# SERIALIO.net
KiCad netlist of a schematic drawn in Altium Designer
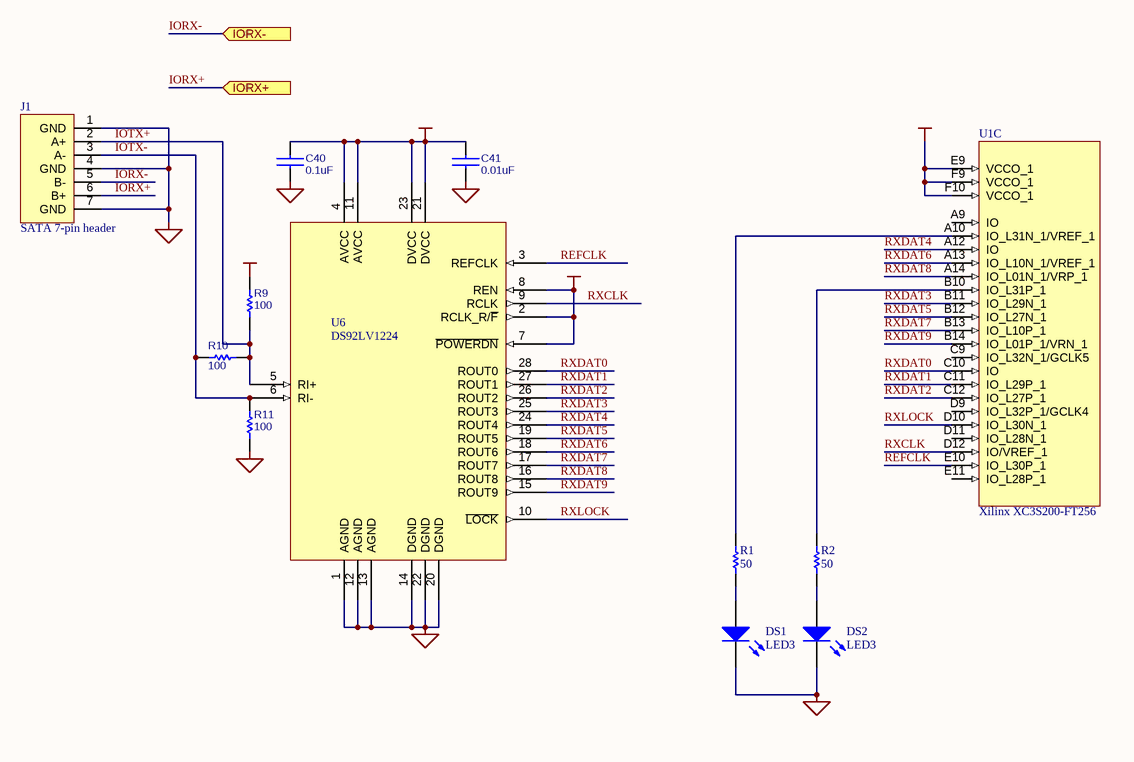
[diagram p0: SERIALIO.SCHDOC]

(export (version "E")
  (design (tool "Eeschema 10.0.6"))
  (components
    (comp (ref "C40")
      (value "0.1uF")
      (footprint "0603")
      (description "Standard Capacitor")
      (fields (field (name "Comment") "CAPACITOR"))
      (libsource (lib "parts") (part "CAPACITOR"))
    )
    (comp (ref "C41")
      (value "0.01uF")
      (footprint "0402")
      (description "Standard Capacitor")
      (fields (field (name "Comment") "CAPACITOR"))
      (libsource (lib "parts") (part "CAPACITOR"))
    )
    (comp (ref "DS1")
      (value "LED3")
      (footprint "SMD _LED")
      (description "Typical BLUE SiC LED")
      (fields (field (name "PUBLISHER") "Altium Limited"))
      (libsource (lib "Miscellaneous Devices") (part "LED3"))
    )
    (comp (ref "DS2")
      (value "LED3")
      (footprint "SMD _LED")
      (description "Typical BLUE SiC LED")
      (fields (field (name "PUBLISHER") "Altium Limited"))
      (libsource (lib "Miscellaneous Devices") (part "LED3"))
    )
    (comp (ref "J1")
      (value "SATA 7-pin header")
      (footprint "MOLES 67800-5005")
      (libsource (lib "parts") (part "SATA-7"))
    )
    (comp (ref "R1")
      (value "50")
      (footprint "0603")
      (description "Standard Passive Resistor")
      (fields (field (name "Comment") "current-limiting series res"))
      (libsource (lib "parts") (part "RESISTOR"))
    )
    (comp (ref "R2")
      (value "50")
      (footprint "0603")
      (description "Standard Passive Resistor")
      (fields (field (name "Comment") "current-limiting series res"))
      (libsource (lib "parts") (part "RESISTOR"))
    )
    (comp (ref "R9")
      (value "100")
      (footprint "0603")
      (description "Standard Passive Resistor")
      (libsource (lib "parts") (part "RESISTOR"))
    )
    (comp (ref "R10")
      (value "100")
      (footprint "0603")
      (description "Standard Passive Resistor")
      (libsource (lib "parts") (part "RESISTOR"))
    )
    (comp (ref "R11")
      (value "100")
      (footprint "0603")
      (description "Standard Passive Resistor")
      (libsource (lib "parts") (part "RESISTOR"))
    )
    (comp (ref "U1")
      (value "Xilinx XC3S200-FT256")
      (footprint "Xilinx FT256 BGA")
      (description "Xilinx Spartan-3 FPGA")
      (libsource (lib "parts") (part "XC3S200-FT256"))
    )
    (comp (ref "U6")
      (value "DS92LV1224")
      (footprint "SSO-G28/E4.3")
      (description "30-66 MHz 10-Bit Bus LVDS Deserializer")
      (libsource (lib "parts") (part "DS92LV1224"))
    )
  )
  (nets
    (net (code "1") (name "/IORX+") (class "Default")
      (node (ref "J1") (pin "6") (pinfunction "B+_6") (pintype "passive"))
    )
    (net (code "2") (name "/IORX-") (class "Default")
      (node (ref "J1") (pin "5") (pinfunction "B-_5") (pintype "passive"))
    )
    (net (code "3") (name "/IOTX+") (class "Default")
      (node (ref "J1") (pin "2") (pinfunction "A+_2") (pintype "passive"))
      (node (ref "R10") (pin "2") (pintype "passive"))
      (node (ref "R9") (pin "2") (pintype "passive"))
      (node (ref "U6") (pin "5") (pinfunction "RI+_5") (pintype "input"))
    )
    (net (code "4") (name "/IOTX-") (class "Default")
      (node (ref "J1") (pin "3") (pinfunction "A-_3") (pintype "passive"))
      (node (ref "R10") (pin "1") (pintype "passive"))
      (node (ref "R11") (pin "2") (pintype "passive"))
      (node (ref "U6") (pin "6") (pinfunction "RI-_6") (pintype "input"))
    )
    (net (code "5") (name "/REFCLK") (class "Default")
      (node (ref "U1") (pin "E10") (pinfunction "IO_L30P_1_E10") (pintype "input"))
      (node (ref "U6") (pin "3") (pinfunction "REFCLK_3") (pintype "input"))
    )
    (net (code "6") (name "/RXCLK") (class "Default")
      (node (ref "U1") (pin "D12") (pinfunction "IO/VREF_1_D12") (pintype "input"))
      (node (ref "U6") (pin "9") (pinfunction "RCLK_9") (pintype "output"))
    )
    (net (code "7") (name "/RXDAT0") (class "Default")
      (node (ref "U1") (pin "C10") (pinfunction "IO_C10") (pintype "input"))
      (node (ref "U6") (pin "28") (pinfunction "ROUT0_28") (pintype "output"))
    )
    (net (code "8") (name "/RXDAT1") (class "Default")
      (node (ref "U1") (pin "C11") (pinfunction "IO_L29P_1_C11") (pintype "input"))
      (node (ref "U6") (pin "27") (pinfunction "ROUT1_27") (pintype "output"))
    )
    (net (code "9") (name "/RXDAT2") (class "Default")
      (node (ref "U1") (pin "C12") (pinfunction "IO_L27P_1_C12") (pintype "input"))
      (node (ref "U6") (pin "26") (pinfunction "ROUT2_26") (pintype "output"))
    )
    (net (code "10") (name "/RXDAT3") (class "Default")
      (node (ref "U1") (pin "B11") (pinfunction "IO_L29N_1_B11") (pintype "input"))
      (node (ref "U6") (pin "25") (pinfunction "ROUT3_25") (pintype "output"))
    )
    (net (code "11") (name "/RXDAT4") (class "Default")
      (node (ref "U1") (pin "A12") (pinfunction "IO_A12") (pintype "input"))
      (node (ref "U6") (pin "24") (pinfunction "ROUT4_24") (pintype "output"))
    )
    (net (code "12") (name "/RXDAT5") (class "Default")
      (node (ref "U1") (pin "B12") (pinfunction "IO_L27N_1_B12") (pintype "input"))
      (node (ref "U6") (pin "19") (pinfunction "ROUT5_19") (pintype "output"))
    )
    (net (code "13") (name "/RXDAT6") (class "Default")
      (node (ref "U1") (pin "A13") (pinfunction "IO_L10N_1/VREF_1_A13") (pintype "input"))
      (node (ref "U6") (pin "18") (pinfunction "ROUT6_18") (pintype "output"))
    )
    (net (code "14") (name "/RXDAT7") (class "Default")
      (node (ref "U1") (pin "B13") (pinfunction "IO_L10P_1_B13") (pintype "input"))
      (node (ref "U6") (pin "17") (pinfunction "ROUT7_17") (pintype "output"))
    )
    (net (code "15") (name "/RXDAT8") (class "Default")
      (node (ref "U1") (pin "A14") (pinfunction "IO_L01N_1/VRP_1_A14") (pintype "input"))
      (node (ref "U6") (pin "16") (pinfunction "ROUT8_16") (pintype "output"))
    )
    (net (code "16") (name "/RXDAT9") (class "Default")
      (node (ref "U1") (pin "B14") (pinfunction "IO_L01P_1/VRN_1_B14") (pintype "input"))
      (node (ref "U6") (pin "15") (pinfunction "ROUT9_15") (pintype "output"))
    )
    (net (code "17") (name "/RXLOCK") (class "Default")
      (node (ref "U1") (pin "D10") (pinfunction "IO_L30N_1_D10") (pintype "input"))
      (node (ref "U6") (pin "10") (pinfunction "~{LOCK}_10") (pintype "output"))
    )
    (net (code "18") (name "GND") (class "Default")
      (node (ref "C40") (pin "1") (pintype "passive"))
      (node (ref "C41") (pin "1") (pintype "passive"))
      (node (ref "DS1") (pin "2") (pinfunction "K_2") (pintype "passive"))
      (node (ref "DS2") (pin "2") (pinfunction "K_2") (pintype "passive"))
      (node (ref "J1") (pin "1") (pinfunction "GND_1") (pintype "passive"))
      (node (ref "J1") (pin "4") (pinfunction "GND_4") (pintype "passive"))
      (node (ref "J1") (pin "7") (pinfunction "GND_7") (pintype "passive"))
      (node (ref "R11") (pin "1") (pintype "passive"))
      (node (ref "U6") (pin "1") (pinfunction "AGND_1") (pintype "power_in"))
      (node (ref "U6") (pin "12") (pinfunction "AGND_12") (pintype "power_in"))
      (node (ref "U6") (pin "13") (pinfunction "AGND_13") (pintype "power_in"))
      (node (ref "U6") (pin "14") (pinfunction "DGND_14") (pintype "power_in"))
      (node (ref "U6") (pin "20") (pinfunction "DGND_20") (pintype "power_in"))
      (node (ref "U6") (pin "22") (pinfunction "DGND_22") (pintype "power_in"))
    )
    (net (code "19") (name "Net-(DS1-A)") (class "Default")
      (node (ref "DS1") (pin "1") (pinfunction "A_1") (pintype "passive"))
      (node (ref "R1") (pin "2") (pintype "passive"))
    )
    (net (code "20") (name "Net-(DS2-A)") (class "Default")
      (node (ref "DS2") (pin "1") (pinfunction "A_1") (pintype "passive"))
      (node (ref "R2") (pin "2") (pintype "passive"))
    )
    (net (code "21") (name "Net-(U1C-IO_L31N_1{slash}VREF_1)") (class "Default")
      (node (ref "R1") (pin "1") (pintype "passive"))
      (node (ref "U1") (pin "A10") (pinfunction "IO_L31N_1/VREF_1_A10") (pintype "input"))
    )
    (net (code "22") (name "Net-(U1C-IO_L31P_1)") (class "Default")
      (node (ref "R2") (pin "1") (pintype "passive"))
      (node (ref "U1") (pin "B10") (pinfunction "IO_L31P_1_B10") (pintype "input"))
    )
    (net (code "23") (name "VCC") (class "Default")
      (node (ref "C40") (pin "2") (pintype "passive"))
      (node (ref "C41") (pin "2") (pintype "passive"))
      (node (ref "R9") (pin "1") (pintype "passive"))
      (node (ref "U1") (pin "E9") (pinfunction "VCCO_1_E9") (pintype "input"))
      (node (ref "U1") (pin "F10") (pinfunction "VCCO_1_F10") (pintype "input"))
      (node (ref "U1") (pin "F9") (pinfunction "VCCO_1_F9") (pintype "input"))
      (node (ref "U6") (pin "11") (pinfunction "AVCC_11") (pintype "power_in"))
      (node (ref "U6") (pin "2") (pinfunction "RCLK_R/~{F}_2") (pintype "output"))
      (node (ref "U6") (pin "21") (pinfunction "DVCC_21") (pintype "power_in"))
      (node (ref "U6") (pin "23") (pinfunction "DVCC_23") (pintype "power_in"))
      (node (ref "U6") (pin "4") (pinfunction "AVCC_4") (pintype "power_in"))
      (node (ref "U6") (pin "7") (pinfunction "~{POWERDN}_7") (pintype "input"))
      (node (ref "U6") (pin "8") (pinfunction "REN_8") (pintype "input"))
    )
    (net (code "24") (name "unconnected-(U1C-IO-PadA9)") (class "Default")
      (node (ref "U1") (pin "A9") (pinfunction "IO_A9") (pintype "input"))
    )
    (net (code "25") (name "unconnected-(U1C-IO_L28N_1-PadD11)") (class "Default")
      (node (ref "U1") (pin "D11") (pinfunction "IO_L28N_1_D11") (pintype "input"))
    )
    (net (code "26") (name "unconnected-(U1C-IO_L28P_1-PadE11)") (class "Default")
      (node (ref "U1") (pin "E11") (pinfunction "IO_L28P_1_E11") (pintype "input"))
    )
    (net (code "27") (name "unconnected-(U1C-IO_L32N_1{slash}GCLK5-PadC9)") (class "Default")
      (node (ref "U1") (pin "C9") (pinfunction "IO_L32N_1/GCLK5_C9") (pintype "input"))
    )
    (net (code "28") (name "unconnected-(U1C-IO_L32P_1{slash}GCLK4-PadD9)") (class "Default")
      (node (ref "U1") (pin "D9") (pinfunction "IO_L32P_1/GCLK4_D9") (pintype "input"))
    )
  )
)
